# PCI_Ponte_retificadora.net
KiCad netlist of a schematic drawn in EasyEDA Pro
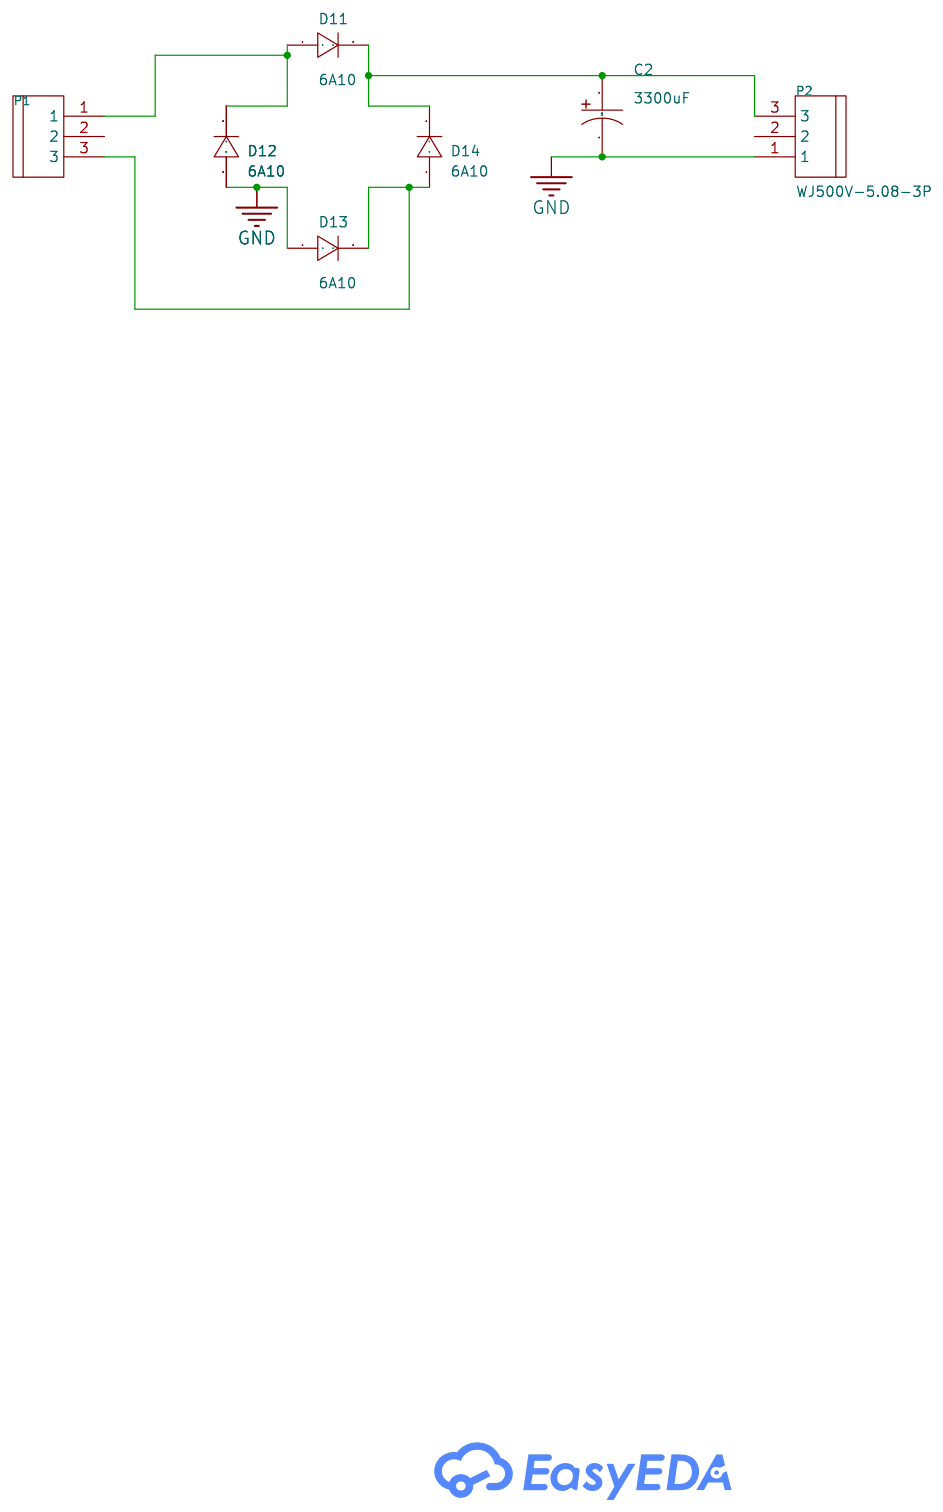
[diagram p0: schematic sheet]

(export (version "E")
  (design (tool "Eeschema 10.0.6"))
  (components
    (comp (ref "C2")
      (value "3300uF")
      (footprint "easyedapro:CAP-TH_BD40.0-P10.00-D2.3-FD")
      (fields
        (field (name "Manufacturer Part") "RP2G561MT350S68CE0")
        (field (name "Manufacturer") "HUAWEI(华威集团)")
      )
      (libsource (lib "easyedapro") (part "RP2G561MT350S68CE0"))
    )
    (comp (ref "D11")
      (value "6A10")
      (footprint "easyedapro:R-6_BD9.0-L9.0-W9.0-P15.00-D1.7-FD")
      (fields (field (name "Manufacturer") "MDD(辰达半导体)"))
      (libsource (lib "easyedapro") (part "6A10_C2461"))
    )
    (comp (ref "D12")
      (value "6A10")
      (footprint "easyedapro:R-6_BD9.0-L9.0-W9.0-P15.00-D1.7-FD")
      (fields (field (name "Manufacturer") "MDD(辰达半导体)"))
      (libsource (lib "easyedapro") (part "6A10_C2461"))
    )
    (comp (ref "D13")
      (value "6A10")
      (footprint "easyedapro:R-6_BD9.0-L9.0-W9.0-P15.00-D1.7-FD")
      (fields (field (name "Manufacturer") "MDD(辰达半导体)"))
      (libsource (lib "easyedapro") (part "6A10_C2461"))
    )
    (comp (ref "D14")
      (value "6A10")
      (footprint "easyedapro:R-6_BD9.0-L9.0-W9.0-P15.00-D1.7-FD")
      (fields (field (name "Manufacturer") "MDD(辰达半导体)"))
      (libsource (lib "easyedapro") (part "6A10_C2461"))
    )
    (comp (ref "P1")
      (value "WJ500V-5.08-3P")
      (footprint "easyedapro:CONN-TH_3P-P5.00_WJ500V-5.08-3P")
      (fields (field (name "Manufacturer") "KANGNEX(康奈克斯电气)"))
      (libsource (lib "easyedapro") (part "WJ500V-5.08-3P-14-00A"))
    )
    (comp (ref "P2")
      (value "WJ500V-5.08-3P")
      (footprint "easyedapro:CONN-TH_3P-P5.00_WJ500V-5.08-3P")
      (fields (field (name "Manufacturer") "KANGNEX(康奈克斯电气)"))
      (libsource (lib "easyedapro") (part "WJ500V-5.08-3P-14-00A"))
    )
  )
  (nets
    (net (code "1") (name "GND") (class "Default")
      (node (ref "C2") (pin "2") (pinfunction "2_2") (pintype "input"))
      (node (ref "D12") (pin "1") (pinfunction "A_1") (pintype "unspecified"))
      (node (ref "D13") (pin "1") (pinfunction "A_1") (pintype "unspecified"))
      (node (ref "P2") (pin "1") (pinfunction "1_1") (pintype "input"))
    )
    (net (code "2") (name "Net-(D11-A)") (class "Default")
      (node (ref "D11") (pin "1") (pinfunction "A_1") (pintype "unspecified"))
      (node (ref "D12") (pin "2") (pinfunction "K_2") (pintype "unspecified"))
      (node (ref "P1") (pin "1") (pinfunction "1_1") (pintype "input"))
    )
    (net (code "3") (name "Net-(D11-K)") (class "Default")
      (node (ref "C2") (pin "1") (pinfunction "1_1") (pintype "input"))
      (node (ref "D11") (pin "2") (pinfunction "K_2") (pintype "unspecified"))
      (node (ref "D14") (pin "2") (pinfunction "K_2") (pintype "unspecified"))
      (node (ref "P2") (pin "3") (pinfunction "3_3") (pintype "input"))
    )
    (net (code "4") (name "Net-(D13-K)") (class "Default")
      (node (ref "D13") (pin "2") (pinfunction "K_2") (pintype "unspecified"))
      (node (ref "D14") (pin "1") (pinfunction "A_1") (pintype "unspecified"))
      (node (ref "P1") (pin "3") (pinfunction "3_3") (pintype "input"))
    )
    (net (code "5") (name "unconnected-(P1-Pad2)") (class "Default")
      (node (ref "P1") (pin "2") (pinfunction "2_2") (pintype "input"))
    )
    (net (code "6") (name "unconnected-(P2-Pad2)") (class "Default")
      (node (ref "P2") (pin "2") (pinfunction "2_2") (pintype "input"))
    )
  )
)
